# 1_0.net
KiCad netlist of a schematic drawn in EAGLE
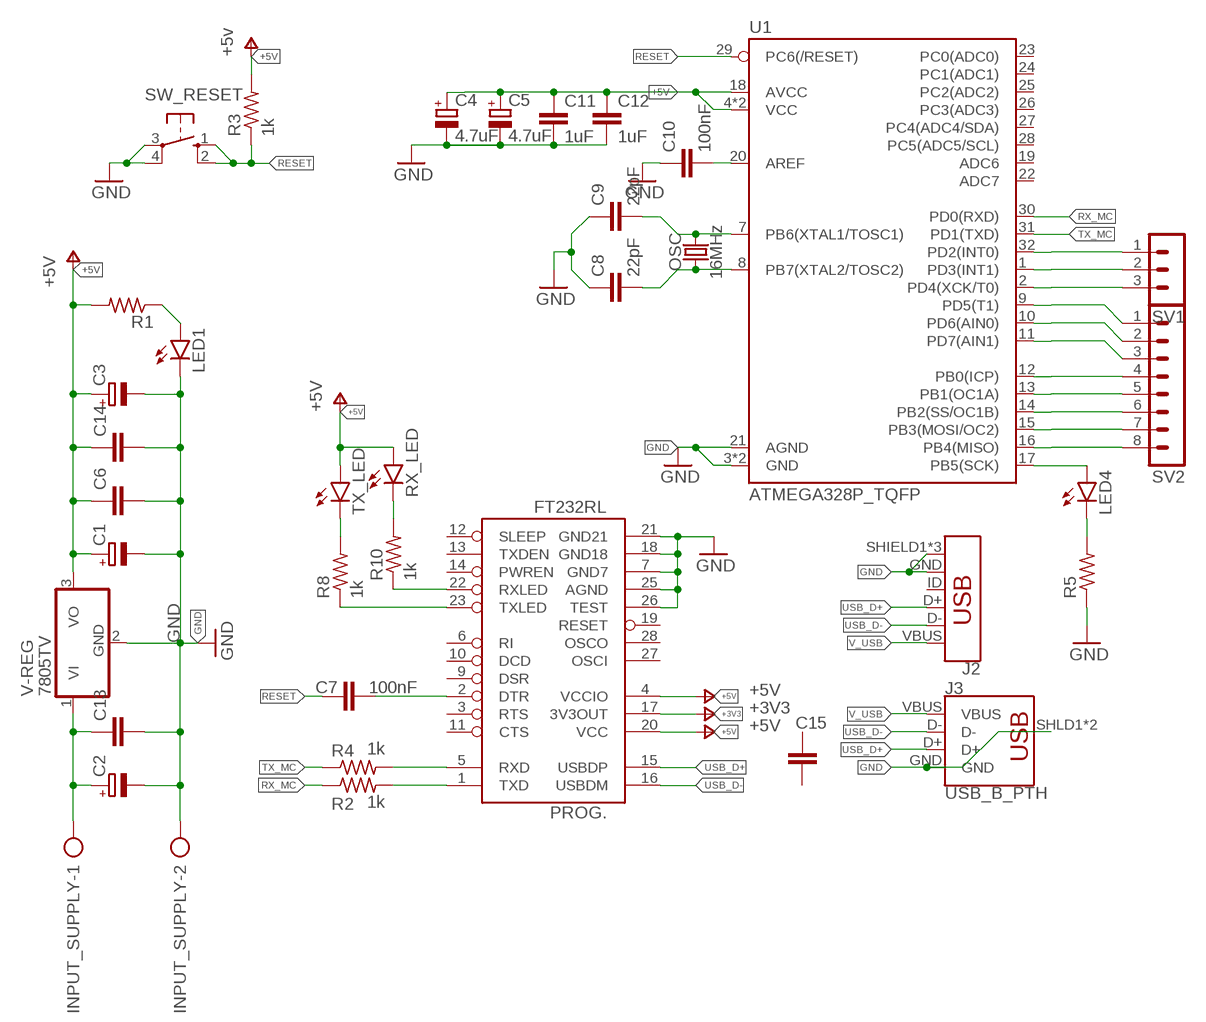
[diagram p0: schematic, sheet 1]

(export (version "E")
  (design (tool "Eeschema 10.0.6"))
  (components
    (comp (ref "C1")
      (value "CPOL-EUE5-10.5")
      (footprint "eagle-import:E5-10,5")
      (libsource (lib "eagle-import") (part "CPOL-EUE5-10.5"))
    )
    (comp (ref "C2")
      (value "CPOL-EUE5-10.5")
      (footprint "eagle-import:E5-10,5")
      (libsource (lib "eagle-import") (part "CPOL-EUE5-10.5"))
    )
    (comp (ref "C3")
      (value "CPOL-EUE5-10.5")
      (footprint "eagle-import:E5-10,5")
      (libsource (lib "eagle-import") (part "CPOL-EUE5-10.5"))
    )
    (comp (ref "C4")
      (value "4.7uF")
      (footprint "eagle-import:E5-10,5")
      (libsource (lib "eagle-import") (part "CPOL-EUE5-10.5"))
    )
    (comp (ref "C5")
      (value "4.7uF")
      (footprint "eagle-import:E5-10,5")
      (libsource (lib "eagle-import") (part "CPOL-EUE5-10.5"))
    )
    (comp (ref "C6")
      (value "C-EU050-030X075")
      (footprint "eagle-import:C050-030X075")
      (libsource (lib "eagle-import") (part "C-EU050-030X075"))
    )
    (comp (ref "C7")
      (value "100nF")
      (footprint "eagle-import:C050-030X075")
      (libsource (lib "eagle-import") (part "C-EU050-030X075"))
    )
    (comp (ref "C8")
      (value "22pF")
      (footprint "eagle-import:C050-030X075")
      (libsource (lib "eagle-import") (part "C-EU050-030X075"))
    )
    (comp (ref "C9")
      (value "22pF")
      (footprint "eagle-import:C050-030X075")
      (libsource (lib "eagle-import") (part "C-EU050-030X075"))
    )
    (comp (ref "C10")
      (value "100nF")
      (footprint "eagle-import:C050-030X075")
      (libsource (lib "eagle-import") (part "C-EU050-030X075"))
    )
    (comp (ref "C11")
      (value "1uF")
      (footprint "eagle-import:C050-030X075")
      (libsource (lib "eagle-import") (part "C-EU050-030X075"))
    )
    (comp (ref "C12")
      (value "1uF")
      (footprint "eagle-import:C050-030X075")
      (libsource (lib "eagle-import") (part "C-EU050-030X075"))
    )
    (comp (ref "C13")
      (value "C-EU050-030X075")
      (footprint "eagle-import:C050-030X075")
      (libsource (lib "eagle-import") (part "C-EU050-030X075"))
    )
    (comp (ref "C14")
      (value "C-EU050-030X075")
      (footprint "eagle-import:C050-030X075")
      (libsource (lib "eagle-import") (part "C-EU050-030X075"))
    )
    (comp (ref "C15")
      (value "C-EU050-030X075")
      (footprint "eagle-import:C050-030X075")
      (libsource (lib "eagle-import") (part "C-EU050-030X075"))
    )
    (comp (ref "INPUT_SUPPLY")
      (value "SMKDSP_1,5/2")
      (footprint "eagle-import:SMKDSP_1,5_2")
      (fields (field (name "MF") "FARNELL") (field (name "MPN") "1733570"))
      (libsource (lib "eagle-import") (part "SMKDSP_1,5/2"))
    )
    (comp (ref "J2")
      (value "USB_MICRO-B_FEMALE-SMT")
      (footprint "eagle-import:USB-B-MICRO-SMD")
      (libsource (lib "eagle-import") (part "USB_MICRO-B_FEMALE-SMT"))
    )
    (comp (ref "J3")
      (value "USB_B_PTH")
      (footprint "eagle-import:USB-B-PTH")
      (libsource (lib "eagle-import") (part "USB_B_PTH"))
    )
    (comp (ref "LED1")
      (value "LED5MM")
      (footprint "eagle-import:LED5MM")
      (libsource (lib "eagle-import") (part "LED5MM"))
    )
    (comp (ref "LED4")
      (value "LED5MM")
      (footprint "eagle-import:LED5MM")
      (libsource (lib "eagle-import") (part "LED5MM"))
    )
    (comp (ref "OSC")
      (value "16MHz")
      (footprint "eagle-import:HC49U")
      (libsource (lib "eagle-import") (part "CRYSTALPTH-HC49UV"))
    )
    (comp (ref "PROG.")
      (value "FT232RL")
      (footprint "eagle-import:SSOP28DB")
      (libsource (lib "eagle-import") (part "FT232RLSSOP"))
    )
    (comp (ref "R1")
      (value "R-US_0207/10")
      (footprint "eagle-import:0207_10")
      (libsource (lib "eagle-import") (part "R-US_0207/10"))
    )
    (comp (ref "R2")
      (value "1k")
      (footprint "eagle-import:0207_10")
      (libsource (lib "eagle-import") (part "R-US_0207/10"))
    )
    (comp (ref "R3")
      (value "1k")
      (footprint "eagle-import:0207_10")
      (libsource (lib "eagle-import") (part "R-US_0207/10"))
    )
    (comp (ref "R4")
      (value "1k")
      (footprint "eagle-import:0207_10")
      (libsource (lib "eagle-import") (part "R-US_0207/10"))
    )
    (comp (ref "R5")
      (value "R-US_0207/10")
      (footprint "eagle-import:0207_10")
      (libsource (lib "eagle-import") (part "R-US_0207/10"))
    )
    (comp (ref "R8")
      (value "1k")
      (footprint "eagle-import:0207_10")
      (libsource (lib "eagle-import") (part "R-US_0207/10"))
    )
    (comp (ref "R10")
      (value "1k")
      (footprint "eagle-import:0207_10")
      (libsource (lib "eagle-import") (part "R-US_0207/10"))
    )
    (comp (ref "RX_LED")
      (value "LED5MM")
      (footprint "eagle-import:LED5MM")
      (libsource (lib "eagle-import") (part "LED5MM"))
    )
    (comp (ref "SV1")
      (value "MA03-1")
      (footprint "eagle-import:MA03-1")
      (libsource (lib "eagle-import") (part "MA03-1"))
    )
    (comp (ref "SV2")
      (value "MA08-1")
      (footprint "eagle-import:MA08-1")
      (libsource (lib "eagle-import") (part "MA08-1"))
    )
    (comp (ref "SW_RESET")
      (value "10-XX")
      (footprint "eagle-import:B3F-10XX")
      (fields (field (name "MPN") "B3F-1000"))
      (libsource (lib "eagle-import") (part "10-XX"))
    )
    (comp (ref "TX_LED")
      (value "LED5MM")
      (footprint "eagle-import:LED5MM")
      (libsource (lib "eagle-import") (part "LED5MM"))
    )
    (comp (ref "U1")
      (value "ATMEGA328P_TQFP")
      (footprint "eagle-import:TQFP32-08")
      (libsource (lib "eagle-import") (part "ATMEGA328P_TQFP"))
    )
    (comp (ref "V-REG")
      (value "7805TV")
      (footprint "eagle-import:TO220V")
      (libsource (lib "eagle-import") (part "78TV05"))
    )
  )
  (nets
    (net (code "1") (name "+3V3") (class "Default")
      (node (ref "PROG.") (pin "17") (pinfunction "3V3OUT_17") (pintype "output"))
    )
    (net (code "2") (name "+5V") (class "Default")
      (node (ref "C1") (pin "+") (pinfunction "+_+") (pintype "passive"))
      (node (ref "C11") (pin "1") (pinfunction "1_1") (pintype "passive"))
      (node (ref "C12") (pin "1") (pinfunction "1_1") (pintype "passive"))
      (node (ref "C14") (pin "1") (pinfunction "1_1") (pintype "passive"))
      (node (ref "C3") (pin "+") (pinfunction "+_+") (pintype "passive"))
      (node (ref "C4") (pin "+") (pinfunction "+_+") (pintype "passive"))
      (node (ref "C5") (pin "+") (pinfunction "+_+") (pintype "passive"))
      (node (ref "C6") (pin "1") (pinfunction "1_1") (pintype "passive"))
      (node (ref "PROG.") (pin "20") (pinfunction "VCC_20") (pintype "power_in"))
      (node (ref "PROG.") (pin "4") (pinfunction "VCCIO_4") (pintype "power_in"))
      (node (ref "R1") (pin "2") (pinfunction "2_2") (pintype "passive"))
      (node (ref "R3") (pin "2") (pinfunction "2_2") (pintype "passive"))
      (node (ref "RX_LED") (pin "A") (pinfunction "A_A") (pintype "passive"))
      (node (ref "TX_LED") (pin "A") (pinfunction "A_A") (pintype "passive"))
      (node (ref "U1") (pin "18") (pinfunction "AVCC_18") (pintype "bidirectional"))
      (node (ref "U1") (pin "4") (pinfunction "VCC_4") (pintype "bidirectional"))
      (node (ref "U1") (pin "6") (pinfunction "VCC_6") (pintype "bidirectional"))
      (node (ref "V-REG") (pin "3") (pinfunction "VO_3") (pintype "passive"))
    )
    (net (code "3") (name "GND") (class "Default")
      (node (ref "C1") (pin "-") (pinfunction "-_-") (pintype "passive"))
      (node (ref "C10") (pin "1") (pinfunction "1_1") (pintype "passive"))
      (node (ref "C11") (pin "2") (pinfunction "2_2") (pintype "passive"))
      (node (ref "C12") (pin "2") (pinfunction "2_2") (pintype "passive"))
      (node (ref "C13") (pin "2") (pinfunction "2_2") (pintype "passive"))
      (node (ref "C14") (pin "2") (pinfunction "2_2") (pintype "passive"))
      (node (ref "C2") (pin "-") (pinfunction "-_-") (pintype "passive"))
      (node (ref "C3") (pin "-") (pinfunction "-_-") (pintype "passive"))
      (node (ref "C4") (pin "-") (pinfunction "-_-") (pintype "passive"))
      (node (ref "C5") (pin "-") (pinfunction "-_-") (pintype "passive"))
      (node (ref "C6") (pin "2") (pinfunction "2_2") (pintype "passive"))
      (node (ref "C8") (pin "1") (pinfunction "1_1") (pintype "passive"))
      (node (ref "C9") (pin "1") (pinfunction "1_1") (pintype "passive"))
      (node (ref "INPUT_SUPPLY") (pin "2") (pinfunction "KL_2") (pintype "passive"))
      (node (ref "J2") (pin "GND") (pinfunction "GND_GND") (pintype "power_in"))
      (node (ref "J2") (pin "SHIELD1") (pinfunction "SHIELD_SHIELD1") (pintype "bidirectional"))
      (node (ref "J2") (pin "SHIELD2") (pinfunction "SHIELD_SHIELD2") (pintype "bidirectional"))
      (node (ref "J2") (pin "SHIELD3") (pinfunction "SHIELD_SHIELD3") (pintype "bidirectional"))
      (node (ref "J3") (pin "GND") (pinfunction "GND_GND") (pintype "power_in"))
      (node (ref "J3") (pin "SHLD1") (pinfunction "SHIELD_SHLD1") (pintype "bidirectional"))
      (node (ref "J3") (pin "SHLD2") (pinfunction "SHIELD_SHLD2") (pintype "bidirectional"))
      (node (ref "LED1") (pin "K") (pinfunction "C_K") (pintype "passive"))
      (node (ref "PROG.") (pin "18") (pinfunction "GND18_18") (pintype "power_in"))
      (node (ref "PROG.") (pin "21") (pinfunction "GND21_21") (pintype "power_in"))
      (node (ref "PROG.") (pin "25") (pinfunction "AGND_25") (pintype "power_in"))
      (node (ref "PROG.") (pin "26") (pinfunction "TEST_26") (pintype "input"))
      (node (ref "PROG.") (pin "7") (pinfunction "GND7_7") (pintype "power_in"))
      (node (ref "R5") (pin "1") (pinfunction "1_1") (pintype "passive"))
      (node (ref "SW_RESET") (pin "3") (pinfunction "P_3") (pintype "passive"))
      (node (ref "SW_RESET") (pin "4") (pinfunction "P1_4") (pintype "passive"))
      (node (ref "U1") (pin "21") (pinfunction "AGND_21") (pintype "bidirectional"))
      (node (ref "U1") (pin "3") (pinfunction "GND_3") (pintype "bidirectional"))
      (node (ref "U1") (pin "5") (pinfunction "GND_5") (pintype "bidirectional"))
      (node (ref "V-REG") (pin "2") (pinfunction "GND_2") (pintype "passive"))
    )
    (net (code "4") (name "Net-(INPUT_SUPPLYA-KL)") (class "Default")
      (node (ref "C13") (pin "1") (pinfunction "1_1") (pintype "passive"))
      (node (ref "C2") (pin "+") (pinfunction "+_+") (pintype "passive"))
      (node (ref "INPUT_SUPPLY") (pin "1") (pinfunction "KL_1") (pintype "passive"))
      (node (ref "V-REG") (pin "1") (pinfunction "VI_1") (pintype "input"))
    )
    (net (code "5") (name "Net-(LED1-PadA)") (class "Default")
      (node (ref "LED1") (pin "A") (pinfunction "A_A") (pintype "passive"))
      (node (ref "R1") (pin "1") (pinfunction "1_1") (pintype "passive"))
    )
    (net (code "6") (name "Net-(LED4-C)") (class "Default")
      (node (ref "LED4") (pin "K") (pinfunction "C_K") (pintype "passive"))
      (node (ref "R5") (pin "2") (pinfunction "2_2") (pintype "passive"))
    )
    (net (code "7") (name "Net-(PROG.-DTR)") (class "Default")
      (node (ref "C7") (pin "2") (pinfunction "2_2") (pintype "passive"))
      (node (ref "PROG.") (pin "2") (pinfunction "DTR_2") (pintype "output"))
    )
    (net (code "8") (name "Net-(PROG.-RXD)") (class "Default")
      (node (ref "PROG.") (pin "5") (pinfunction "RXD_5") (pintype "input"))
      (node (ref "R4") (pin "2") (pinfunction "2_2") (pintype "passive"))
    )
    (net (code "9") (name "Net-(PROG.-RXLED)") (class "Default")
      (node (ref "PROG.") (pin "22") (pinfunction "RXLED_22") (pintype "input"))
      (node (ref "R10") (pin "1") (pinfunction "1_1") (pintype "passive"))
    )
    (net (code "10") (name "Net-(PROG.-TXD)") (class "Default")
      (node (ref "PROG.") (pin "1") (pinfunction "TXD_1") (pintype "output"))
      (node (ref "R2") (pin "2") (pinfunction "2_2") (pintype "passive"))
    )
    (net (code "11") (name "Net-(PROG.-TXLED)") (class "Default")
      (node (ref "PROG.") (pin "23") (pinfunction "TXLED_23") (pintype "input"))
      (node (ref "R8") (pin "1") (pinfunction "1_1") (pintype "passive"))
    )
    (net (code "12") (name "Net-(RX_LED-C)") (class "Default")
      (node (ref "R10") (pin "2") (pinfunction "2_2") (pintype "passive"))
      (node (ref "RX_LED") (pin "K") (pinfunction "C_K") (pintype "passive"))
    )
    (net (code "13") (name "Net-(TX_LED-C)") (class "Default")
      (node (ref "R8") (pin "2") (pinfunction "2_2") (pintype "passive"))
      (node (ref "TX_LED") (pin "K") (pinfunction "C_K") (pintype "passive"))
    )
    (net (code "14") (name "Net-(U1-AREF)") (class "Default")
      (node (ref "C10") (pin "2") (pinfunction "2_2") (pintype "passive"))
      (node (ref "U1") (pin "20") (pinfunction "AREF_20") (pintype "bidirectional"))
    )
    (net (code "15") (name "Net-(U1-PB0(ICP))") (class "Default")
      (node (ref "SV2") (pin "4") (pinfunction "4_4") (pintype "passive"))
      (node (ref "U1") (pin "12") (pinfunction "PB0(ICP)_12") (pintype "bidirectional"))
    )
    (net (code "16") (name "Net-(U1-PB1(OC1A))") (class "Default")
      (node (ref "SV2") (pin "5") (pinfunction "5_5") (pintype "passive"))
      (node (ref "U1") (pin "13") (pinfunction "PB1(OC1A)_13") (pintype "bidirectional"))
    )
    (net (code "17") (name "Net-(U1-PB2(SS{slash}OC1B))") (class "Default")
      (node (ref "SV2") (pin "6") (pinfunction "6_6") (pintype "passive"))
      (node (ref "U1") (pin "14") (pinfunction "PB2(SS/OC1B)_14") (pintype "bidirectional"))
    )
    (net (code "18") (name "Net-(U1-PB3(MOSI{slash}OC2))") (class "Default")
      (node (ref "SV2") (pin "7") (pinfunction "7_7") (pintype "passive"))
      (node (ref "U1") (pin "15") (pinfunction "PB3(MOSI/OC2)_15") (pintype "bidirectional"))
    )
    (net (code "19") (name "Net-(U1-PB4(MISO))") (class "Default")
      (node (ref "SV2") (pin "8") (pinfunction "8_8") (pintype "passive"))
      (node (ref "U1") (pin "16") (pinfunction "PB4(MISO)_16") (pintype "bidirectional"))
    )
    (net (code "20") (name "Net-(U1-PB5(SCK))") (class "Default")
      (node (ref "LED4") (pin "A") (pinfunction "A_A") (pintype "passive"))
      (node (ref "U1") (pin "17") (pinfunction "PB5(SCK)_17") (pintype "bidirectional"))
    )
    (net (code "21") (name "Net-(U1-PB6(XTAL1{slash}TOSC1))") (class "Default")
      (node (ref "C9") (pin "2") (pinfunction "2_2") (pintype "passive"))
      (node (ref "OSC") (pin "2") (pinfunction "2_2") (pintype "passive"))
      (node (ref "U1") (pin "7") (pinfunction "PB6(XTAL1/TOSC1)_7") (pintype "bidirectional"))
    )
    (net (code "22") (name "Net-(U1-PB7(XTAL2{slash}TOSC2))") (class "Default")
      (node (ref "C8") (pin "2") (pinfunction "2_2") (pintype "passive"))
      (node (ref "OSC") (pin "1") (pinfunction "1_1") (pintype "passive"))
      (node (ref "U1") (pin "8") (pinfunction "PB7(XTAL2/TOSC2)_8") (pintype "bidirectional"))
    )
    (net (code "23") (name "Net-(U1-PD2(INT0))") (class "Default")
      (node (ref "SV1") (pin "1") (pinfunction "1_1") (pintype "passive"))
      (node (ref "U1") (pin "32") (pinfunction "PD2(INT0)_32") (pintype "bidirectional"))
    )
    (net (code "24") (name "Net-(U1-PD3(INT1))") (class "Default")
      (node (ref "SV1") (pin "2") (pinfunction "2_2") (pintype "passive"))
      (node (ref "U1") (pin "1") (pinfunction "PD3(INT1)_1") (pintype "bidirectional"))
    )
    (net (code "25") (name "Net-(U1-PD4(XCK{slash}T0))") (class "Default")
      (node (ref "SV1") (pin "3") (pinfunction "3_3") (pintype "passive"))
      (node (ref "U1") (pin "2") (pinfunction "PD4(XCK/T0)_2") (pintype "bidirectional"))
    )
    (net (code "26") (name "Net-(U1-PD5(T1))") (class "Default")
      (node (ref "SV2") (pin "1") (pinfunction "1_1") (pintype "passive"))
      (node (ref "U1") (pin "9") (pinfunction "PD5(T1)_9") (pintype "bidirectional"))
    )
    (net (code "27") (name "Net-(U1-PD6(AIN0))") (class "Default")
      (node (ref "SV2") (pin "2") (pinfunction "2_2") (pintype "passive"))
      (node (ref "U1") (pin "10") (pinfunction "PD6(AIN0)_10") (pintype "bidirectional"))
    )
    (net (code "28") (name "Net-(U1-PD7(AIN1))") (class "Default")
      (node (ref "SV2") (pin "3") (pinfunction "3_3") (pintype "passive"))
      (node (ref "U1") (pin "11") (pinfunction "PD7(AIN1)_11") (pintype "bidirectional"))
    )
    (net (code "29") (name "RESET") (class "Default")
      (node (ref "C7") (pin "1") (pinfunction "1_1") (pintype "passive"))
      (node (ref "R3") (pin "1") (pinfunction "1_1") (pintype "passive"))
      (node (ref "SW_RESET") (pin "1") (pinfunction "S_1") (pintype "passive"))
      (node (ref "SW_RESET") (pin "2") (pinfunction "S1_2") (pintype "passive"))
      (node (ref "U1") (pin "29") (pinfunction "PC6(/RESET)_29") (pintype "bidirectional"))
    )
    (net (code "30") (name "RX_MC") (class "Default")
      (node (ref "R2") (pin "1") (pinfunction "1_1") (pintype "passive"))
      (node (ref "U1") (pin "30") (pinfunction "PD0(RXD)_30") (pintype "bidirectional"))
    )
    (net (code "31") (name "TX_MC") (class "Default")
      (node (ref "R4") (pin "1") (pinfunction "1_1") (pintype "passive"))
      (node (ref "U1") (pin "31") (pinfunction "PD1(TXD)_31") (pintype "bidirectional"))
    )
    (net (code "32") (name "USB_D+") (class "Default")
      (node (ref "J2") (pin "D+") (pinfunction "D+_D+") (pintype "bidirectional"))
      (node (ref "J3") (pin "D+") (pinfunction "D+_D+") (pintype "bidirectional"))
      (node (ref "PROG.") (pin "15") (pinfunction "USBDP_15") (pintype "bidirectional"))
    )
    (net (code "33") (name "USB_D-") (class "Default")
      (node (ref "J2") (pin "D-") (pinfunction "D-_D-") (pintype "bidirectional"))
      (node (ref "J3") (pin "D-") (pinfunction "D-_D-") (pintype "bidirectional"))
      (node (ref "PROG.") (pin "16") (pinfunction "USBDM_16") (pintype "bidirectional"))
    )
    (net (code "34") (name "V_USB") (class "Default")
      (node (ref "J2") (pin "VBUS") (pinfunction "VBUS_VBUS") (pintype "power_in"))
      (node (ref "J3") (pin "VBUS") (pinfunction "VBUS_VBUS") (pintype "power_in"))
    )
    (net (code "35") (name "unconnected-(C15-Pad1)") (class "Default")
      (node (ref "C15") (pin "1") (pinfunction "1_1") (pintype "passive"))
    )
    (net (code "36") (name "unconnected-(C15-Pad2)") (class "Default")
      (node (ref "C15") (pin "2") (pinfunction "2_2") (pintype "passive"))
    )
    (net (code "37") (name "unconnected-(J2-PadID)") (class "Default")
      (node (ref "J2") (pin "ID") (pinfunction "ID_ID") (pintype "bidirectional"))
    )
    (net (code "38") (name "unconnected-(PROG.-CTS-Pad11)") (class "Default")
      (node (ref "PROG.") (pin "11") (pinfunction "CTS_11") (pintype "input"))
    )
    (net (code "39") (name "unconnected-(PROG.-DCD-Pad10)") (class "Default")
      (node (ref "PROG.") (pin "10") (pinfunction "DCD_10") (pintype "input"))
    )
    (net (code "40") (name "unconnected-(PROG.-DSR-Pad9)") (class "Default")
      (node (ref "PROG.") (pin "9") (pinfunction "DSR_9") (pintype "input"))
    )
    (net (code "41") (name "unconnected-(PROG.-OSCI-Pad27)") (class "Default")
      (node (ref "PROG.") (pin "27") (pinfunction "OSCI_27") (pintype "input"))
    )
    (net (code "42") (name "unconnected-(PROG.-OSCO-Pad28)") (class "Default")
      (node (ref "PROG.") (pin "28") (pinfunction "OSCO_28") (pintype "output"))
    )
    (net (code "43") (name "unconnected-(PROG.-PWREN-Pad14)") (class "Default")
      (node (ref "PROG.") (pin "14") (pinfunction "PWREN_14") (pintype "input"))
    )
    (net (code "44") (name "unconnected-(PROG.-RESET-Pad19)") (class "Default")
      (node (ref "PROG.") (pin "19") (pinfunction "RESET_19") (pintype "input"))
    )
    (net (code "45") (name "unconnected-(PROG.-RI-Pad6)") (class "Default")
      (node (ref "PROG.") (pin "6") (pinfunction "RI_6") (pintype "input"))
    )
    (net (code "46") (name "unconnected-(PROG.-RTS-Pad3)") (class "Default")
      (node (ref "PROG.") (pin "3") (pinfunction "RTS_3") (pintype "output"))
    )
    (net (code "47") (name "unconnected-(PROG.-SLEEP-Pad12)") (class "Default")
      (node (ref "PROG.") (pin "12") (pinfunction "SLEEP_12") (pintype "input"))
    )
    (net (code "48") (name "unconnected-(PROG.-TXDEN-Pad13)") (class "Default")
      (node (ref "PROG.") (pin "13") (pinfunction "TXDEN_13") (pintype "input"))
    )
    (net (code "49") (name "unconnected-(U1-ADC6-Pad19)") (class "Default")
      (node (ref "U1") (pin "19") (pinfunction "ADC6_19") (pintype "bidirectional"))
    )
    (net (code "50") (name "unconnected-(U1-ADC7-Pad22)") (class "Default")
      (node (ref "U1") (pin "22") (pinfunction "ADC7_22") (pintype "bidirectional"))
    )
    (net (code "51") (name "unconnected-(U1-PC0(ADC0)-Pad23)") (class "Default")
      (node (ref "U1") (pin "23") (pinfunction "PC0(ADC0)_23") (pintype "bidirectional"))
    )
    (net (code "52") (name "unconnected-(U1-PC1(ADC1)-Pad24)") (class "Default")
      (node (ref "U1") (pin "24") (pinfunction "PC1(ADC1)_24") (pintype "bidirectional"))
    )
    (net (code "53") (name "unconnected-(U1-PC2(ADC2)-Pad25)") (class "Default")
      (node (ref "U1") (pin "25") (pinfunction "PC2(ADC2)_25") (pintype "bidirectional"))
    )
    (net (code "54") (name "unconnected-(U1-PC3(ADC3)-Pad26)") (class "Default")
      (node (ref "U1") (pin "26") (pinfunction "PC3(ADC3)_26") (pintype "bidirectional"))
    )
    (net (code "55") (name "unconnected-(U1-PC4(ADC4{slash}SDA)-Pad27)") (class "Default")
      (node (ref "U1") (pin "27") (pinfunction "PC4(ADC4/SDA)_27") (pintype "bidirectional"))
    )
    (net (code "56") (name "unconnected-(U1-PC5(ADC5{slash}SCL)-Pad28)") (class "Default")
      (node (ref "U1") (pin "28") (pinfunction "PC5(ADC5/SCL)_28") (pintype "bidirectional"))
    )
  )
)
